# Signalni_dio.net
KiCad netlist of a schematic drawn in Altium Designer
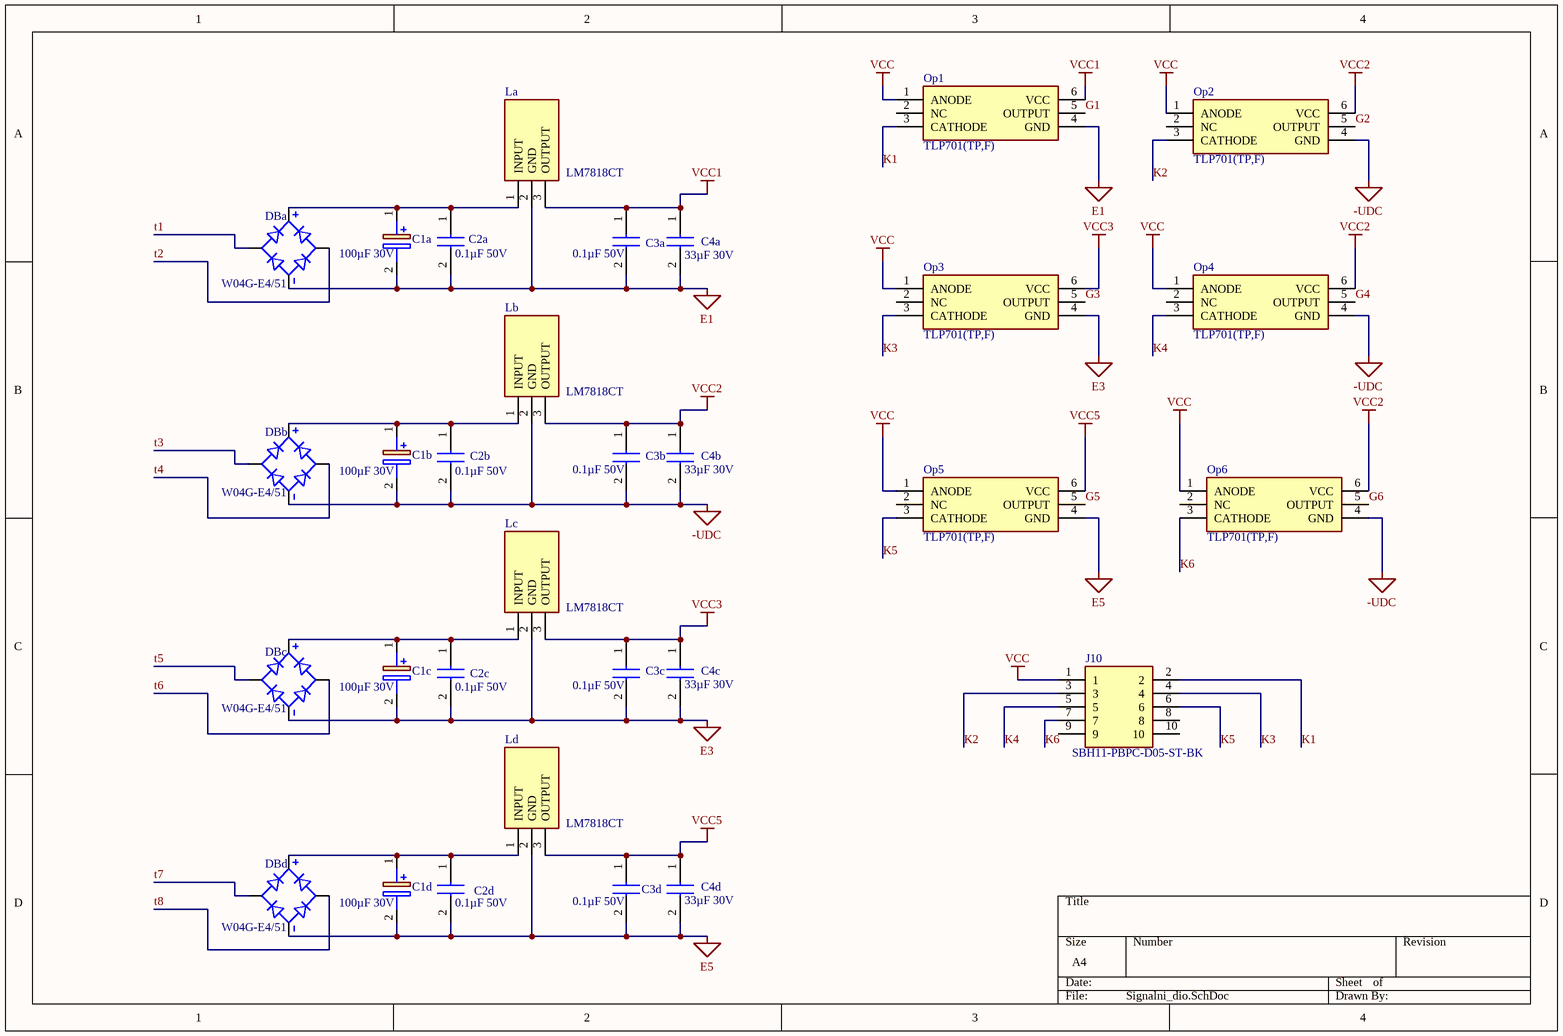
[diagram p0: Signalni_dio.SchDoc]

(export (version "E")
  (design (tool "Eeschema 10.0.6"))
  (components
    (comp (ref "C1a")
      (value "100µF 30V")
      (footprint "20")
      (description "Capacitor Polarised")
      (fields
        (field (name "MANUFACTURER_PART_NUMBER") "ESK107M035AE3AA")
        (field (name "MOUSER PART NUMBER") "80-ESK107M035AE3AA")
      )
      (libsource (lib "Trofazni_invertor_SchLib") (part "ESK107M035AE3AA"))
    )
    (comp (ref "C1b")
      (value "100µF 30V")
      (footprint "20")
      (description "Capacitor Polarised")
      (fields
        (field (name "MANUFACTURER_PART_NUMBER") "ESK107M035AE3AA")
        (field (name "MOUSER PART NUMBER") "80-ESK107M035AE3AA")
      )
      (libsource (lib "Trofazni_invertor_SchLib") (part "ESK107M035AE3AA"))
    )
    (comp (ref "C1c")
      (value "100µF 30V")
      (footprint "20")
      (description "Capacitor Polarised")
      (fields
        (field (name "MANUFACTURER_PART_NUMBER") "ESK107M035AE3AA")
        (field (name "MOUSER PART NUMBER") "80-ESK107M035AE3AA")
      )
      (libsource (lib "Trofazni_invertor_SchLib") (part "ESK107M035AE3AA"))
    )
    (comp (ref "C1d")
      (value "100µF 30V")
      (footprint "20")
      (description "Capacitor Polarised")
      (fields
        (field (name "MANUFACTURER_PART_NUMBER") "ESK107M035AE3AA")
        (field (name "MOUSER PART NUMBER") "80-ESK107M035AE3AA")
      )
      (libsource (lib "Trofazni_invertor_SchLib") (part "ESK107M035AE3AA"))
    )
    (comp (ref "C2a")
      (value "0.1µF 50V")
      (footprint "8")
      (description "Capacitor")
      (fields
        (field (name "MANUFACTURER_PART_NUMBER") "K104Z15Y5VF5TL2")
        (field (name "MOUSER PART NUMBER") "594-K104Z15Y5VF5TL2")
      )
      (libsource (lib "Trofazni_invertor_SchLib") (part "K104Z15Y5VF5TL2"))
    )
    (comp (ref "C2b")
      (value "0.1µF 50V")
      (footprint "8")
      (description "Capacitor")
      (fields
        (field (name "MANUFACTURER_PART_NUMBER") "K104Z15Y5VF5TL2")
        (field (name "MOUSER PART NUMBER") "594-K104Z15Y5VF5TL2")
      )
      (libsource (lib "Trofazni_invertor_SchLib") (part "K104Z15Y5VF5TL2"))
    )
    (comp (ref "C2c")
      (value "0.1µF 50V")
      (footprint "8")
      (description "Capacitor")
      (fields
        (field (name "MANUFACTURER_PART_NUMBER") "K104Z15Y5VF5TL2")
        (field (name "MOUSER PART NUMBER") "594-K104Z15Y5VF5TL2")
      )
      (libsource (lib "Trofazni_invertor_SchLib") (part "K104Z15Y5VF5TL2"))
    )
    (comp (ref "C2d")
      (value "0.1µF 50V")
      (footprint "8")
      (description "Capacitor")
      (fields
        (field (name "MANUFACTURER_PART_NUMBER") "K104Z15Y5VF5TL2")
        (field (name "MOUSER PART NUMBER") "594-K104Z15Y5VF5TL2")
      )
      (libsource (lib "Trofazni_invertor_SchLib") (part "K104Z15Y5VF5TL2"))
    )
    (comp (ref "C3a")
      (value "0.1µF 50V")
      (footprint "8")
      (description "Capacitor")
      (fields
        (field (name "MANUFACTURER_PART_NUMBER") "K104Z15Y5VF5TL2")
        (field (name "MOUSER PART NUMBER") "594-K104Z15Y5VF5TL2")
      )
      (libsource (lib "Trofazni_invertor_SchLib") (part "K104Z15Y5VF5TL2_1"))
    )
    (comp (ref "C3b")
      (value "0.1µF 50V")
      (footprint "8")
      (description "Capacitor")
      (fields
        (field (name "MANUFACTURER_PART_NUMBER") "K104Z15Y5VF5TL2")
        (field (name "MOUSER PART NUMBER") "594-K104Z15Y5VF5TL2")
      )
      (libsource (lib "Trofazni_invertor_SchLib") (part "K104Z15Y5VF5TL2_1"))
    )
    (comp (ref "C3c")
      (value "0.1µF 50V")
      (footprint "8")
      (description "Capacitor")
      (fields
        (field (name "MANUFACTURER_PART_NUMBER") "K104Z15Y5VF5TL2")
        (field (name "MOUSER PART NUMBER") "594-K104Z15Y5VF5TL2")
      )
      (libsource (lib "Trofazni_invertor_SchLib") (part "K104Z15Y5VF5TL2_1"))
    )
    (comp (ref "C3d")
      (value "0.1µF 50V")
      (footprint "8")
      (description "Capacitor")
      (fields
        (field (name "MANUFACTURER_PART_NUMBER") "K104Z15Y5VF5TL2")
        (field (name "MOUSER PART NUMBER") "594-K104Z15Y5VF5TL2")
      )
      (libsource (lib "Trofazni_invertor_SchLib") (part "K104Z15Y5VF5TL2_1"))
    )
    (comp (ref "C4a")
      (value "33µF 30V")
      (footprint "SamacSys:CAPPRD200W50D500H1250")
      (description "Capacitor")
      (fields
        (field (name "MANUFACTURER_PART_NUMBER") "ESH336M035AC3AA")
        (field (name "MOUSER PART NUMBER") "80-ESH336M035AC3AA")
      )
      (libsource (lib "Trofazni_invertor_SchLib") (part "ESH336M035AC3AA"))
    )
    (comp (ref "C4b")
      (value "33µF 30V")
      (footprint "SamacSys:CAPPRD200W50D500H1250")
      (description "Capacitor")
      (fields
        (field (name "MANUFACTURER_PART_NUMBER") "ESH336M035AC3AA")
        (field (name "MOUSER PART NUMBER") "80-ESH336M035AC3AA")
      )
      (libsource (lib "Trofazni_invertor_SchLib") (part "ESH336M035AC3AA"))
    )
    (comp (ref "C4c")
      (value "33µF 30V")
      (footprint "SamacSys:CAPPRD200W50D500H1250")
      (description "Capacitor")
      (fields
        (field (name "MANUFACTURER_PART_NUMBER") "ESH336M035AC3AA")
        (field (name "MOUSER PART NUMBER") "80-ESH336M035AC3AA")
      )
      (libsource (lib "Trofazni_invertor_SchLib") (part "ESH336M035AC3AA"))
    )
    (comp (ref "C4d")
      (value "33µF 30V")
      (footprint "SamacSys:CAPPRD200W50D500H1250")
      (description "Capacitor")
      (fields
        (field (name "MANUFACTURER_PART_NUMBER") "ESH336M035AC3AA")
        (field (name "MOUSER PART NUMBER") "80-ESH336M035AC3AA")
      )
      (libsource (lib "Trofazni_invertor_SchLib") (part "ESH336M035AC3AA"))
    )
    (comp (ref "DBa")
      (value "W04G-E4/51")
      (footprint "11")
      (description "Bridge Rectifier Single Phase Standard 400 V Through Hole WOG")
      (fields (field (name "MF") "Vishay"))
      (libsource (lib "Trofazni_invertor_SchLib") (part "W04G-E4/51"))
    )
    (comp (ref "DBb")
      (value "W04G-E4/51")
      (footprint "11")
      (description "Bridge Rectifier Single Phase Standard 400 V Through Hole WOG")
      (fields (field (name "MF") "Vishay"))
      (libsource (lib "Trofazni_invertor_SchLib") (part "W04G-E4/51"))
    )
    (comp (ref "DBc")
      (value "W04G-E4/51")
      (footprint "11")
      (description "Bridge Rectifier Single Phase Standard 400 V Through Hole WOG")
      (fields (field (name "MF") "Vishay"))
      (libsource (lib "Trofazni_invertor_SchLib") (part "W04G-E4/51"))
    )
    (comp (ref "DBd")
      (value "W04G-E4/51")
      (footprint "11")
      (description "Bridge Rectifier Single Phase Standard 400 V Through Hole WOG")
      (fields (field (name "MF") "Vishay"))
      (libsource (lib "Trofazni_invertor_SchLib") (part "W04G-E4/51"))
    )
    (comp (ref "J10")
      (value "SBH11-PBPC-D05-ST-BK")
      (footprint "4")
      (description "Connector")
      (libsource (lib "Trofazni_invertor_SchLib") (part "SBH11-PBPC-D05-ST-BK"))
    )
    (comp (ref "La")
      (value "LM7818CT")
      (footprint "9")
      (description "Integrated Circuit")
      (fields (field (name "MOUSER PART NUMBER") "512-LM7818CT"))
      (libsource (lib "Trofazni_invertor_SchLib") (part "LM7818CT"))
    )
    (comp (ref "Lb")
      (value "LM7818CT")
      (footprint "9")
      (description "Integrated Circuit")
      (fields (field (name "MOUSER PART NUMBER") "512-LM7818CT"))
      (libsource (lib "Trofazni_invertor_SchLib") (part "LM7818CT"))
    )
    (comp (ref "Lc")
      (value "LM7818CT")
      (footprint "9")
      (description "Integrated Circuit")
      (fields (field (name "MOUSER PART NUMBER") "512-LM7818CT"))
      (libsource (lib "Trofazni_invertor_SchLib") (part "LM7818CT"))
    )
    (comp (ref "Ld")
      (value "LM7818CT")
      (footprint "9")
      (description "Integrated Circuit")
      (fields (field (name "MOUSER PART NUMBER") "512-LM7818CT"))
      (libsource (lib "Trofazni_invertor_SchLib") (part "LM7818CT"))
    )
    (comp (ref "Op1")
      (value "TLP701(TP,F)")
      (footprint "1")
      (description "Phototransistor")
      (fields (field (name "MANUFACTURER_PART_NUMBER") "TLP701(TP)"))
      (libsource (lib "Trofazni_invertor_SchLib") (part "TLP701_TP_"))
    )
    (comp (ref "Op2")
      (value "TLP701(TP,F)")
      (footprint "1")
      (description "Phototransistor")
      (fields (field (name "MANUFACTURER_PART_NUMBER") "TLP701(TP)"))
      (libsource (lib "Trofazni_invertor_SchLib") (part "TLP701_TP_"))
    )
    (comp (ref "Op3")
      (value "TLP701(TP,F)")
      (footprint "1")
      (description "Phototransistor")
      (fields (field (name "MANUFACTURER_PART_NUMBER") "TLP701(TP)"))
      (libsource (lib "Trofazni_invertor_SchLib") (part "TLP701_TP_"))
    )
    (comp (ref "Op4")
      (value "TLP701(TP,F)")
      (footprint "1")
      (description "Phototransistor")
      (fields (field (name "MANUFACTURER_PART_NUMBER") "TLP701(TP)"))
      (libsource (lib "Trofazni_invertor_SchLib") (part "TLP701_TP_"))
    )
    (comp (ref "Op5")
      (value "TLP701(TP,F)")
      (footprint "1")
      (description "Phototransistor")
      (fields (field (name "MANUFACTURER_PART_NUMBER") "TLP701(TP)"))
      (libsource (lib "Trofazni_invertor_SchLib") (part "TLP701_TP_"))
    )
    (comp (ref "Op6")
      (value "TLP701(TP,F)")
      (footprint "1")
      (description "Phototransistor")
      (fields (field (name "MANUFACTURER_PART_NUMBER") "TLP701(TP)"))
      (libsource (lib "Trofazni_invertor_SchLib") (part "TLP701_TP_"))
    )
  )
  (nets
    (net (code "1") (name "-UDC") (class "Default")
      (node (ref "C1b") (pin "2") (pinfunction "-_2") (pintype "passive"))
      (node (ref "C2b") (pin "2") (pinfunction "-_2") (pintype "passive"))
      (node (ref "C3b") (pin "2") (pinfunction "-_2") (pintype "passive"))
      (node (ref "C4b") (pin "2") (pinfunction "-_2") (pintype "passive"))
      (node (ref "DBb") (pin "NEG") (pinfunction "NEG_NEG") (pintype "passive"))
      (node (ref "Lb") (pin "2") (pinfunction "GND_2") (pintype "passive"))
      (node (ref "Op2") (pin "4") (pinfunction "GND_4") (pintype "passive"))
      (node (ref "Op4") (pin "4") (pinfunction "GND_4") (pintype "passive"))
      (node (ref "Op6") (pin "4") (pinfunction "GND_4") (pintype "passive"))
    )
    (net (code "2") (name "/G1") (class "Default")
      (node (ref "Op1") (pin "5") (pinfunction "OUTPUT_5") (pintype "passive"))
    )
    (net (code "3") (name "/G2") (class "Default")
      (node (ref "Op2") (pin "5") (pinfunction "OUTPUT_5") (pintype "passive"))
    )
    (net (code "4") (name "/G3") (class "Default")
      (node (ref "Op3") (pin "5") (pinfunction "OUTPUT_5") (pintype "passive"))
    )
    (net (code "5") (name "/G4") (class "Default")
      (node (ref "Op4") (pin "5") (pinfunction "OUTPUT_5") (pintype "passive"))
    )
    (net (code "6") (name "/G5") (class "Default")
      (node (ref "Op5") (pin "5") (pinfunction "OUTPUT_5") (pintype "passive"))
    )
    (net (code "7") (name "/G6") (class "Default")
      (node (ref "Op6") (pin "5") (pinfunction "OUTPUT_5") (pintype "passive"))
    )
    (net (code "8") (name "/K1") (class "Default")
      (node (ref "J10") (pin "2") (pinfunction "2_2") (pintype "passive"))
      (node (ref "Op1") (pin "3") (pinfunction "CATHODE_3") (pintype "passive"))
    )
    (net (code "9") (name "/K2") (class "Default")
      (node (ref "J10") (pin "3") (pinfunction "3_3") (pintype "passive"))
      (node (ref "Op2") (pin "3") (pinfunction "CATHODE_3") (pintype "passive"))
    )
    (net (code "10") (name "/K3") (class "Default")
      (node (ref "J10") (pin "4") (pinfunction "4_4") (pintype "passive"))
      (node (ref "Op3") (pin "3") (pinfunction "CATHODE_3") (pintype "passive"))
    )
    (net (code "11") (name "/K4") (class "Default")
      (node (ref "J10") (pin "5") (pinfunction "5_5") (pintype "passive"))
      (node (ref "Op4") (pin "3") (pinfunction "CATHODE_3") (pintype "passive"))
    )
    (net (code "12") (name "/K5") (class "Default")
      (node (ref "J10") (pin "6") (pinfunction "6_6") (pintype "passive"))
      (node (ref "Op5") (pin "3") (pinfunction "CATHODE_3") (pintype "passive"))
    )
    (net (code "13") (name "/K6") (class "Default")
      (node (ref "J10") (pin "7") (pinfunction "7_7") (pintype "passive"))
      (node (ref "Op6") (pin "3") (pinfunction "CATHODE_3") (pintype "passive"))
    )
    (net (code "14") (name "/t1") (class "Default")
      (node (ref "DBa") (pin "AC2") (pinfunction "AC2_AC2") (pintype "passive"))
    )
    (net (code "15") (name "/t2") (class "Default")
      (node (ref "DBa") (pin "AC1") (pinfunction "AC1_AC1") (pintype "passive"))
    )
    (net (code "16") (name "/t3") (class "Default")
      (node (ref "DBb") (pin "AC2") (pinfunction "AC2_AC2") (pintype "passive"))
    )
    (net (code "17") (name "/t4") (class "Default")
      (node (ref "DBb") (pin "AC1") (pinfunction "AC1_AC1") (pintype "passive"))
    )
    (net (code "18") (name "/t5") (class "Default")
      (node (ref "DBc") (pin "AC2") (pinfunction "AC2_AC2") (pintype "passive"))
    )
    (net (code "19") (name "/t6") (class "Default")
      (node (ref "DBc") (pin "AC1") (pinfunction "AC1_AC1") (pintype "passive"))
    )
    (net (code "20") (name "/t7") (class "Default")
      (node (ref "DBd") (pin "AC2") (pinfunction "AC2_AC2") (pintype "passive"))
    )
    (net (code "21") (name "/t8") (class "Default")
      (node (ref "DBd") (pin "AC1") (pinfunction "AC1_AC1") (pintype "passive"))
    )
    (net (code "22") (name "E1") (class "Default")
      (node (ref "C1a") (pin "2") (pinfunction "-_2") (pintype "passive"))
      (node (ref "C2a") (pin "2") (pinfunction "-_2") (pintype "passive"))
      (node (ref "C3a") (pin "2") (pinfunction "-_2") (pintype "passive"))
      (node (ref "C4a") (pin "2") (pinfunction "-_2") (pintype "passive"))
      (node (ref "DBa") (pin "NEG") (pinfunction "NEG_NEG") (pintype "passive"))
      (node (ref "La") (pin "2") (pinfunction "GND_2") (pintype "passive"))
      (node (ref "Op1") (pin "4") (pinfunction "GND_4") (pintype "passive"))
    )
    (net (code "23") (name "E3") (class "Default")
      (node (ref "C1c") (pin "2") (pinfunction "-_2") (pintype "passive"))
      (node (ref "C2c") (pin "2") (pinfunction "-_2") (pintype "passive"))
      (node (ref "C3c") (pin "2") (pinfunction "-_2") (pintype "passive"))
      (node (ref "C4c") (pin "2") (pinfunction "-_2") (pintype "passive"))
      (node (ref "DBc") (pin "NEG") (pinfunction "NEG_NEG") (pintype "passive"))
      (node (ref "Lc") (pin "2") (pinfunction "GND_2") (pintype "passive"))
      (node (ref "Op3") (pin "4") (pinfunction "GND_4") (pintype "passive"))
    )
    (net (code "24") (name "E5") (class "Default")
      (node (ref "C1d") (pin "2") (pinfunction "-_2") (pintype "passive"))
      (node (ref "C2d") (pin "2") (pinfunction "-_2") (pintype "passive"))
      (node (ref "C3d") (pin "2") (pinfunction "-_2") (pintype "passive"))
      (node (ref "C4d") (pin "2") (pinfunction "-_2") (pintype "passive"))
      (node (ref "DBd") (pin "NEG") (pinfunction "NEG_NEG") (pintype "passive"))
      (node (ref "Ld") (pin "2") (pinfunction "GND_2") (pintype "passive"))
      (node (ref "Op5") (pin "4") (pinfunction "GND_4") (pintype "passive"))
    )
    (net (code "25") (name "Net-(C1a-+)") (class "Default")
      (node (ref "C1a") (pin "1") (pinfunction "+_1") (pintype "passive"))
      (node (ref "C2a") (pin "1") (pinfunction "+_1") (pintype "passive"))
      (node (ref "DBa") (pin "POS") (pinfunction "POS_POS") (pintype "passive"))
      (node (ref "La") (pin "1") (pinfunction "INPUT_1") (pintype "passive"))
    )
    (net (code "26") (name "Net-(C1b-+)") (class "Default")
      (node (ref "C1b") (pin "1") (pinfunction "+_1") (pintype "passive"))
      (node (ref "C2b") (pin "1") (pinfunction "+_1") (pintype "passive"))
      (node (ref "DBb") (pin "POS") (pinfunction "POS_POS") (pintype "passive"))
      (node (ref "Lb") (pin "1") (pinfunction "INPUT_1") (pintype "passive"))
    )
    (net (code "27") (name "Net-(C1c-+)") (class "Default")
      (node (ref "C1c") (pin "1") (pinfunction "+_1") (pintype "passive"))
      (node (ref "C2c") (pin "1") (pinfunction "+_1") (pintype "passive"))
      (node (ref "DBc") (pin "POS") (pinfunction "POS_POS") (pintype "passive"))
      (node (ref "Lc") (pin "1") (pinfunction "INPUT_1") (pintype "passive"))
    )
    (net (code "28") (name "Net-(C1d-+)") (class "Default")
      (node (ref "C1d") (pin "1") (pinfunction "+_1") (pintype "passive"))
      (node (ref "C2d") (pin "1") (pinfunction "+_1") (pintype "passive"))
      (node (ref "DBd") (pin "POS") (pinfunction "POS_POS") (pintype "passive"))
      (node (ref "Ld") (pin "1") (pinfunction "INPUT_1") (pintype "passive"))
    )
    (net (code "29") (name "VCC") (class "Default")
      (node (ref "J10") (pin "1") (pinfunction "1_1") (pintype "passive"))
      (node (ref "Op1") (pin "1") (pinfunction "ANODE_1") (pintype "passive"))
      (node (ref "Op2") (pin "1") (pinfunction "ANODE_1") (pintype "passive"))
      (node (ref "Op3") (pin "1") (pinfunction "ANODE_1") (pintype "passive"))
      (node (ref "Op4") (pin "1") (pinfunction "ANODE_1") (pintype "passive"))
      (node (ref "Op5") (pin "1") (pinfunction "ANODE_1") (pintype "passive"))
      (node (ref "Op6") (pin "1") (pinfunction "ANODE_1") (pintype "passive"))
    )
    (net (code "30") (name "VCC1") (class "Default")
      (node (ref "C3a") (pin "1") (pinfunction "+_1") (pintype "passive"))
      (node (ref "C4a") (pin "1") (pinfunction "+_1") (pintype "passive"))
      (node (ref "La") (pin "3") (pinfunction "OUTPUT_3") (pintype "passive"))
      (node (ref "Op1") (pin "6") (pinfunction "VCC_6") (pintype "passive"))
    )
    (net (code "31") (name "VCC2") (class "Default")
      (node (ref "C3b") (pin "1") (pinfunction "+_1") (pintype "passive"))
      (node (ref "C4b") (pin "1") (pinfunction "+_1") (pintype "passive"))
      (node (ref "Lb") (pin "3") (pinfunction "OUTPUT_3") (pintype "passive"))
      (node (ref "Op2") (pin "6") (pinfunction "VCC_6") (pintype "passive"))
      (node (ref "Op4") (pin "6") (pinfunction "VCC_6") (pintype "passive"))
      (node (ref "Op6") (pin "6") (pinfunction "VCC_6") (pintype "passive"))
    )
    (net (code "32") (name "VCC3") (class "Default")
      (node (ref "C3c") (pin "1") (pinfunction "+_1") (pintype "passive"))
      (node (ref "C4c") (pin "1") (pinfunction "+_1") (pintype "passive"))
      (node (ref "Lc") (pin "3") (pinfunction "OUTPUT_3") (pintype "passive"))
      (node (ref "Op3") (pin "6") (pinfunction "VCC_6") (pintype "passive"))
    )
    (net (code "33") (name "VCC5") (class "Default")
      (node (ref "C3d") (pin "1") (pinfunction "+_1") (pintype "passive"))
      (node (ref "C4d") (pin "1") (pinfunction "+_1") (pintype "passive"))
      (node (ref "Ld") (pin "3") (pinfunction "OUTPUT_3") (pintype "passive"))
      (node (ref "Op5") (pin "6") (pinfunction "VCC_6") (pintype "passive"))
    )
    (net (code "34") (name "unconnected-(J10-Pad8)") (class "Default")
      (node (ref "J10") (pin "8") (pinfunction "8_8") (pintype "passive"))
    )
    (net (code "35") (name "unconnected-(J10-Pad9)") (class "Default")
      (node (ref "J10") (pin "9") (pinfunction "9_9") (pintype "passive"))
    )
    (net (code "36") (name "unconnected-(J10-Pad10)") (class "Default")
      (node (ref "J10") (pin "10") (pinfunction "10_10") (pintype "passive"))
    )
    (net (code "37") (name "unconnected-(Op1-NC-Pad2)") (class "Default")
      (node (ref "Op1") (pin "2") (pinfunction "NC_2") (pintype "passive"))
    )
    (net (code "38") (name "unconnected-(Op2-NC-Pad2)") (class "Default")
      (node (ref "Op2") (pin "2") (pinfunction "NC_2") (pintype "passive"))
    )
    (net (code "39") (name "unconnected-(Op3-NC-Pad2)") (class "Default")
      (node (ref "Op3") (pin "2") (pinfunction "NC_2") (pintype "passive"))
    )
    (net (code "40") (name "unconnected-(Op4-NC-Pad2)") (class "Default")
      (node (ref "Op4") (pin "2") (pinfunction "NC_2") (pintype "passive"))
    )
    (net (code "41") (name "unconnected-(Op5-NC-Pad2)") (class "Default")
      (node (ref "Op5") (pin "2") (pinfunction "NC_2") (pintype "passive"))
    )
    (net (code "42") (name "unconnected-(Op6-NC-Pad2)") (class "Default")
      (node (ref "Op6") (pin "2") (pinfunction "NC_2") (pintype "passive"))
    )
  )
)
